# A601E.net
KiCad netlist of a schematic drawn in EAGLE
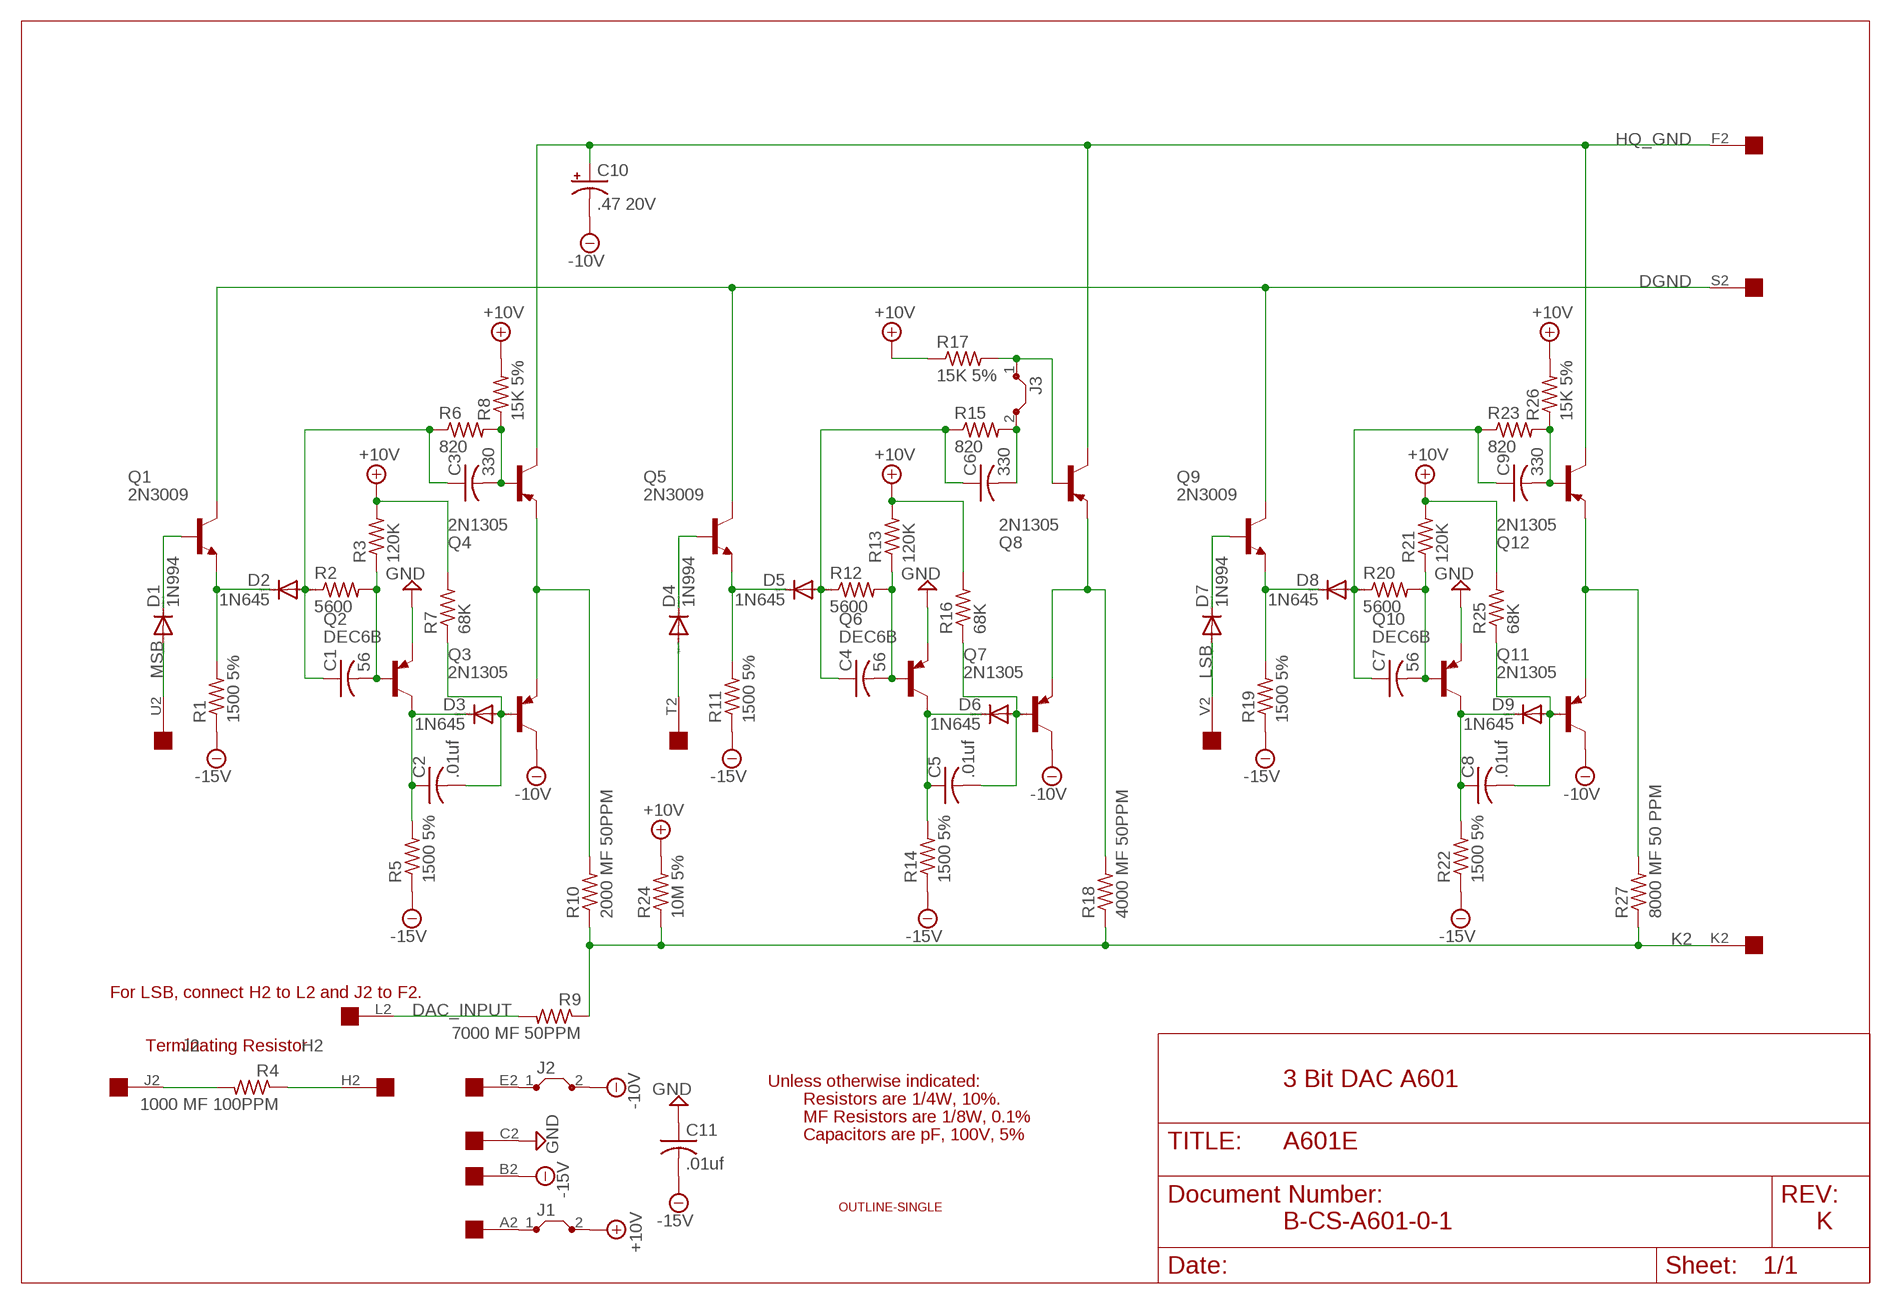
[diagram p0: schematic, sheet 1]

(export (version "E")
  (design (tool "Eeschema 10.0.6"))
  (components
    (comp (ref "C1")
      (value "56")
      (footprint "eagle-import:C075-032X103")
      (libsource (lib "eagle-import") (part "C-US075-032X103"))
    )
    (comp (ref "C2")
      (value ".01uf")
      (footprint "eagle-import:C050-025X075")
      (libsource (lib "eagle-import") (part "C-US050-025X075"))
    )
    (comp (ref "C3")
      (value "330")
      (footprint "eagle-import:C075-032X103")
      (libsource (lib "eagle-import") (part "C-US075-032X103"))
    )
    (comp (ref "C4")
      (value "56")
      (footprint "eagle-import:C075-032X103")
      (libsource (lib "eagle-import") (part "C-US075-032X103"))
    )
    (comp (ref "C5")
      (value ".01uf")
      (footprint "eagle-import:C050-025X075")
      (libsource (lib "eagle-import") (part "C-US050-025X075"))
    )
    (comp (ref "C6")
      (value "330")
      (footprint "eagle-import:C075-032X103")
      (libsource (lib "eagle-import") (part "C-US075-032X103"))
    )
    (comp (ref "C7")
      (value "56")
      (footprint "eagle-import:C075-032X103")
      (libsource (lib "eagle-import") (part "C-US075-032X103"))
    )
    (comp (ref "C8")
      (value ".01uf")
      (footprint "eagle-import:C050-025X075")
      (libsource (lib "eagle-import") (part "C-US050-025X075"))
    )
    (comp (ref "C9")
      (value "330")
      (footprint "eagle-import:C075-032X103")
      (libsource (lib "eagle-import") (part "C-US075-032X103"))
    )
    (comp (ref "C10")
      (value ".47 20V")
      (footprint "eagle-import:E22-6")
      (libsource (lib "eagle-import") (part "CPOL-USE22-6AXIAL"))
    )
    (comp (ref "C11")
      (value ".01uf")
      (footprint "eagle-import:C050-025X075")
      (libsource (lib "eagle-import") (part "C-US050-025X075"))
    )
    (comp (ref "D1")
      (value "1N994")
      (footprint "eagle-import:DO35-10")
      (libsource (lib "eagle-import") (part "1N4148DO35-10"))
    )
    (comp (ref "D2")
      (value "1N645")
      (footprint "eagle-import:DO35-10")
      (libsource (lib "eagle-import") (part "1N4148DO35-10"))
    )
    (comp (ref "D3")
      (value "1N645")
      (footprint "eagle-import:DO35-10")
      (libsource (lib "eagle-import") (part "1N4148DO35-10"))
    )
    (comp (ref "D4")
      (value "1N994")
      (footprint "eagle-import:DO35-10")
      (libsource (lib "eagle-import") (part "1N4148DO35-10"))
    )
    (comp (ref "D5")
      (value "1N645")
      (footprint "eagle-import:DO35-10")
      (libsource (lib "eagle-import") (part "1N4148DO35-10"))
    )
    (comp (ref "D6")
      (value "1N645")
      (footprint "eagle-import:DO35-10")
      (libsource (lib "eagle-import") (part "1N4148DO35-10"))
    )
    (comp (ref "D7")
      (value "1N994")
      (footprint "eagle-import:DO35-10")
      (libsource (lib "eagle-import") (part "1N4148DO35-10"))
    )
    (comp (ref "D8")
      (value "1N645")
      (footprint "eagle-import:DO35-10")
      (libsource (lib "eagle-import") (part "1N4148DO35-10"))
    )
    (comp (ref "D9")
      (value "1N645")
      (footprint "eagle-import:DO35-10")
      (libsource (lib "eagle-import") (part "1N4148DO35-10"))
    )
    (comp (ref "J1")
      (value "J10MM")
      (footprint "eagle-import:10")
      (libsource (lib "eagle-import") (part "J10MM"))
    )
    (comp (ref "J2")
      (value "J10MM")
      (footprint "eagle-import:10")
      (libsource (lib "eagle-import") (part "J10MM"))
    )
    (comp (ref "J3")
      (value "J10MM")
      (footprint "eagle-import:10")
      (libsource (lib "eagle-import") (part "J10MM"))
    )
    (comp (ref "Q1")
      (value "2N3009")
      (footprint "eagle-import:TO39")
      (libsource (lib "eagle-import") (part "-NPN-TO39-EBC2N1613"))
    )
    (comp (ref "Q2")
      (value "DEC6B")
      (footprint "eagle-import:TO39")
      (libsource (lib "eagle-import") (part "2N2904A"))
    )
    (comp (ref "Q3")
      (value "2N1305")
      (footprint "eagle-import:TO39")
      (libsource (lib "eagle-import") (part "2N2904A"))
    )
    (comp (ref "Q4")
      (value "2N1305")
      (footprint "eagle-import:TO39")
      (libsource (lib "eagle-import") (part "2N2904A"))
    )
    (comp (ref "Q5")
      (value "2N3009")
      (footprint "eagle-import:TO39")
      (libsource (lib "eagle-import") (part "-NPN-TO39-EBC2N1613"))
    )
    (comp (ref "Q6")
      (value "DEC6B")
      (footprint "eagle-import:TO39")
      (libsource (lib "eagle-import") (part "2N2904A"))
    )
    (comp (ref "Q7")
      (value "2N1305")
      (footprint "eagle-import:TO39")
      (libsource (lib "eagle-import") (part "2N2904A"))
    )
    (comp (ref "Q8")
      (value "2N1305")
      (footprint "eagle-import:TO39")
      (libsource (lib "eagle-import") (part "2N2904A"))
    )
    (comp (ref "Q9")
      (value "2N3009")
      (footprint "eagle-import:TO39")
      (libsource (lib "eagle-import") (part "-NPN-TO39-EBC2N1613"))
    )
    (comp (ref "Q10")
      (value "DEC6B")
      (footprint "eagle-import:TO39")
      (libsource (lib "eagle-import") (part "2N2904A"))
    )
    (comp (ref "Q11")
      (value "2N1305")
      (footprint "eagle-import:TO39")
      (libsource (lib "eagle-import") (part "2N2904A"))
    )
    (comp (ref "Q12")
      (value "2N1305")
      (footprint "eagle-import:TO39")
      (libsource (lib "eagle-import") (part "2N2904A"))
    )
    (comp (ref "R1")
      (value "1500 5%")
      (footprint "eagle-import:0207_10")
      (libsource (lib "eagle-import") (part "R-US_0207/10"))
    )
    (comp (ref "R2")
      (value "5600")
      (footprint "eagle-import:0207_10")
      (libsource (lib "eagle-import") (part "R-US_0207/10"))
    )
    (comp (ref "R3")
      (value "120K")
      (footprint "eagle-import:0207_10")
      (libsource (lib "eagle-import") (part "R-US_0207/10"))
    )
    (comp (ref "R4")
      (value "1000 MF 100PPM")
      (footprint "eagle-import:0309_12")
      (libsource (lib "eagle-import") (part "R-US_0309/12"))
    )
    (comp (ref "R5")
      (value "1500 5%")
      (footprint "eagle-import:0207_10")
      (libsource (lib "eagle-import") (part "R-US_0207/10"))
    )
    (comp (ref "R6")
      (value "820")
      (footprint "eagle-import:0207_10")
      (libsource (lib "eagle-import") (part "R-US_0207/10"))
    )
    (comp (ref "R7")
      (value "68K")
      (footprint "eagle-import:0207_10")
      (libsource (lib "eagle-import") (part "R-US_0207/10"))
    )
    (comp (ref "R8")
      (value "15K 5%")
      (footprint "eagle-import:0207_10")
      (libsource (lib "eagle-import") (part "R-US_0207/10"))
    )
    (comp (ref "R9")
      (value "7000 MF 50PPM")
      (footprint "eagle-import:0309_12")
      (libsource (lib "eagle-import") (part "R-US_0309/12"))
    )
    (comp (ref "R10")
      (value "2000 MF 50PPM")
      (footprint "eagle-import:0309_12")
      (libsource (lib "eagle-import") (part "R-US_0309/12"))
    )
    (comp (ref "R11")
      (value "1500 5%")
      (footprint "eagle-import:0207_10")
      (libsource (lib "eagle-import") (part "R-US_0207/10"))
    )
    (comp (ref "R12")
      (value "5600")
      (footprint "eagle-import:0207_10")
      (libsource (lib "eagle-import") (part "R-US_0207/10"))
    )
    (comp (ref "R13")
      (value "120K")
      (footprint "eagle-import:0207_10")
      (libsource (lib "eagle-import") (part "R-US_0207/10"))
    )
    (comp (ref "R14")
      (value "1500 5%")
      (footprint "eagle-import:0207_10")
      (libsource (lib "eagle-import") (part "R-US_0207/10"))
    )
    (comp (ref "R15")
      (value "820")
      (footprint "eagle-import:0207_10")
      (libsource (lib "eagle-import") (part "R-US_0207/10"))
    )
    (comp (ref "R16")
      (value "68K")
      (footprint "eagle-import:0207_10")
      (libsource (lib "eagle-import") (part "R-US_0207/10"))
    )
    (comp (ref "R17")
      (value "15K 5%")
      (footprint "eagle-import:0207_10")
      (libsource (lib "eagle-import") (part "R-US_0207/10"))
    )
    (comp (ref "R18")
      (value "4000 MF 50PPM")
      (footprint "eagle-import:0309_12")
      (libsource (lib "eagle-import") (part "R-US_0309/12"))
    )
    (comp (ref "R19")
      (value "1500 5%")
      (footprint "eagle-import:0207_10")
      (libsource (lib "eagle-import") (part "R-US_0207/10"))
    )
    (comp (ref "R20")
      (value "5600")
      (footprint "eagle-import:0207_10")
      (libsource (lib "eagle-import") (part "R-US_0207/10"))
    )
    (comp (ref "R21")
      (value "120K")
      (footprint "eagle-import:0207_10")
      (libsource (lib "eagle-import") (part "R-US_0207/10"))
    )
    (comp (ref "R22")
      (value "1500 5%")
      (footprint "eagle-import:0207_10")
      (libsource (lib "eagle-import") (part "R-US_0207/10"))
    )
    (comp (ref "R23")
      (value "820")
      (footprint "eagle-import:0207_10")
      (libsource (lib "eagle-import") (part "R-US_0207/10"))
    )
    (comp (ref "R24")
      (value "10M 5%")
      (footprint "eagle-import:0207_10")
      (libsource (lib "eagle-import") (part "R-US_0207/10"))
    )
    (comp (ref "R25")
      (value "68K")
      (footprint "eagle-import:0207_10")
      (libsource (lib "eagle-import") (part "R-US_0207/10"))
    )
    (comp (ref "R26")
      (value "15K 5%")
      (footprint "eagle-import:0207_10")
      (libsource (lib "eagle-import") (part "R-US_0207/10"))
    )
    (comp (ref "R27")
      (value "8000 MF 50 PPM")
      (footprint "eagle-import:0309_12")
      (libsource (lib "eagle-import") (part "R-US_0309/12"))
    )
    (comp (ref "U$1")
      (value "OUTLINE-SINGLE")
      (footprint "eagle-import:SINGLE")
      (libsource (lib "eagle-import") (part "OUTLINE-SINGLE"))
    )
    (comp (ref "U$3")
      (value "EDGE-1")
      (footprint "eagle-import:EDGE-CON1")
      (libsource (lib "eagle-import") (part "EDGE-1"))
    )
  )
  (nets
    (net (code "1") (name "+10V") (class "Default")
      (node (ref "J1") (pin "2") (pinfunction "2_2") (pintype "passive"))
      (node (ref "R13") (pin "2") (pinfunction "2_2") (pintype "passive"))
      (node (ref "R16") (pin "2") (pinfunction "2_2") (pintype "passive"))
      (node (ref "R17") (pin "1") (pinfunction "1_1") (pintype "passive"))
      (node (ref "R21") (pin "2") (pinfunction "2_2") (pintype "passive"))
      (node (ref "R24") (pin "2") (pinfunction "2_2") (pintype "passive"))
      (node (ref "R25") (pin "2") (pinfunction "2_2") (pintype "passive"))
      (node (ref "R26") (pin "2") (pinfunction "2_2") (pintype "passive"))
      (node (ref "R3") (pin "2") (pinfunction "2_2") (pintype "passive"))
      (node (ref "R7") (pin "2") (pinfunction "2_2") (pintype "passive"))
      (node (ref "R8") (pin "2") (pinfunction "2_2") (pintype "passive"))
    )
    (net (code "2") (name "-10V") (class "Default")
      (node (ref "C10") (pin "-") (pinfunction "-_-") (pintype "passive"))
      (node (ref "J2") (pin "2") (pinfunction "2_2") (pintype "passive"))
      (node (ref "Q11") (pin "3") (pinfunction "C_3") (pintype "passive"))
      (node (ref "Q3") (pin "3") (pinfunction "C_3") (pintype "passive"))
      (node (ref "Q7") (pin "3") (pinfunction "C_3") (pintype "passive"))
    )
    (net (code "3") (name "-15V") (class "Default")
      (node (ref "C11") (pin "2") (pinfunction "2_2") (pintype "passive"))
      (node (ref "R1") (pin "1") (pinfunction "1_1") (pintype "passive"))
      (node (ref "R11") (pin "1") (pinfunction "1_1") (pintype "passive"))
      (node (ref "R14") (pin "1") (pinfunction "1_1") (pintype "passive"))
      (node (ref "R19") (pin "1") (pinfunction "1_1") (pintype "passive"))
      (node (ref "R22") (pin "1") (pinfunction "1_1") (pintype "passive"))
      (node (ref "R5") (pin "1") (pinfunction "1_1") (pintype "passive"))
      (node (ref "U$3") (pin "B2") (pinfunction "1_B2") (pintype "bidirectional"))
    )
    (net (code "4") (name "/DAC_INPUT") (class "Default")
      (node (ref "R9") (pin "2") (pinfunction "2_2") (pintype "passive"))
      (node (ref "U$3") (pin "L2") (pinfunction "1_L2") (pintype "bidirectional"))
    )
    (net (code "5") (name "/DGND") (class "Default")
      (node (ref "Q1") (pin "3") (pinfunction "C_3") (pintype "passive"))
      (node (ref "Q5") (pin "3") (pinfunction "C_3") (pintype "passive"))
      (node (ref "Q9") (pin "3") (pinfunction "C_3") (pintype "passive"))
      (node (ref "U$3") (pin "S2") (pinfunction "1_S2") (pintype "bidirectional"))
    )
    (net (code "6") (name "/H2") (class "Default")
      (node (ref "R4") (pin "1") (pinfunction "1_1") (pintype "passive"))
      (node (ref "U$3") (pin "H2") (pinfunction "1_H2") (pintype "bidirectional"))
    )
    (net (code "7") (name "/HQ_GND") (class "Default")
      (node (ref "C10") (pin "+") (pinfunction "+_+") (pintype "passive"))
      (node (ref "Q12") (pin "3") (pinfunction "C_3") (pintype "passive"))
      (node (ref "Q4") (pin "3") (pinfunction "C_3") (pintype "passive"))
      (node (ref "Q8") (pin "3") (pinfunction "C_3") (pintype "passive"))
      (node (ref "U$3") (pin "F2") (pinfunction "1_F2") (pintype "bidirectional"))
    )
    (net (code "8") (name "/J2") (class "Default")
      (node (ref "R4") (pin "2") (pinfunction "2_2") (pintype "passive"))
      (node (ref "U$3") (pin "J2") (pinfunction "1_J2") (pintype "bidirectional"))
    )
    (net (code "9") (name "/K2") (class "Default")
      (node (ref "R10") (pin "1") (pinfunction "1_1") (pintype "passive"))
      (node (ref "R18") (pin "1") (pinfunction "1_1") (pintype "passive"))
      (node (ref "R24") (pin "1") (pinfunction "1_1") (pintype "passive"))
      (node (ref "R27") (pin "1") (pinfunction "1_1") (pintype "passive"))
      (node (ref "R9") (pin "1") (pinfunction "1_1") (pintype "passive"))
      (node (ref "U$3") (pin "K2") (pinfunction "1_K2") (pintype "bidirectional"))
    )
    (net (code "10") (name "/LSB") (class "Default")
      (node (ref "D7") (pin "A") (pinfunction "A_A") (pintype "passive"))
      (node (ref "U$3") (pin "V2") (pinfunction "1_V2") (pintype "bidirectional"))
    )
    (net (code "11") (name "/MSB") (class "Default")
      (node (ref "D1") (pin "A") (pinfunction "A_A") (pintype "passive"))
      (node (ref "U$3") (pin "U2") (pinfunction "1_U2") (pintype "bidirectional"))
    )
    (net (code "12") (name "GND") (class "Default")
      (node (ref "C11") (pin "1") (pinfunction "1_1") (pintype "passive"))
      (node (ref "Q10") (pin "1") (pinfunction "E_1") (pintype "passive"))
      (node (ref "Q2") (pin "1") (pinfunction "E_1") (pintype "passive"))
      (node (ref "Q6") (pin "1") (pinfunction "E_1") (pintype "passive"))
      (node (ref "U$3") (pin "C2") (pinfunction "1_C2") (pintype "bidirectional"))
    )
    (net (code "13") (name "Net-(C1-Pad1)") (class "Default")
      (node (ref "C1") (pin "1") (pinfunction "1_1") (pintype "passive"))
      (node (ref "C3") (pin "1") (pinfunction "1_1") (pintype "passive"))
      (node (ref "D2") (pin "A") (pinfunction "A_A") (pintype "passive"))
      (node (ref "R2") (pin "1") (pinfunction "1_1") (pintype "passive"))
      (node (ref "R6") (pin "1") (pinfunction "1_1") (pintype "passive"))
    )
    (net (code "14") (name "Net-(C4-Pad1)") (class "Default")
      (node (ref "C4") (pin "1") (pinfunction "1_1") (pintype "passive"))
      (node (ref "C6") (pin "1") (pinfunction "1_1") (pintype "passive"))
      (node (ref "D5") (pin "A") (pinfunction "A_A") (pintype "passive"))
      (node (ref "R12") (pin "1") (pinfunction "1_1") (pintype "passive"))
      (node (ref "R15") (pin "1") (pinfunction "1_1") (pintype "passive"))
    )
    (net (code "15") (name "Net-(C6-Pad2)") (class "Default")
      (node (ref "C6") (pin "2") (pinfunction "2_2") (pintype "passive"))
      (node (ref "J3") (pin "2") (pinfunction "2_2") (pintype "passive"))
      (node (ref "R15") (pin "2") (pinfunction "2_2") (pintype "passive"))
    )
    (net (code "16") (name "Net-(C7-Pad1)") (class "Default")
      (node (ref "C7") (pin "1") (pinfunction "1_1") (pintype "passive"))
      (node (ref "C9") (pin "1") (pinfunction "1_1") (pintype "passive"))
      (node (ref "D8") (pin "A") (pinfunction "A_A") (pintype "passive"))
      (node (ref "R20") (pin "1") (pinfunction "1_1") (pintype "passive"))
      (node (ref "R23") (pin "1") (pinfunction "1_1") (pintype "passive"))
    )
    (net (code "17") (name "Net-(Q1-B)") (class "Default")
      (node (ref "D1") (pin "C") (pinfunction "C_C") (pintype "passive"))
      (node (ref "Q1") (pin "2") (pinfunction "B_2") (pintype "passive"))
    )
    (net (code "18") (name "Net-(Q1-E)") (class "Default")
      (node (ref "D2") (pin "C") (pinfunction "C_C") (pintype "passive"))
      (node (ref "Q1") (pin "1") (pinfunction "E_1") (pintype "passive"))
      (node (ref "R1") (pin "2") (pinfunction "2_2") (pintype "passive"))
    )
    (net (code "19") (name "Net-(Q2-B)") (class "Default")
      (node (ref "C1") (pin "2") (pinfunction "2_2") (pintype "passive"))
      (node (ref "Q2") (pin "2") (pinfunction "B_2") (pintype "passive"))
      (node (ref "R2") (pin "2") (pinfunction "2_2") (pintype "passive"))
      (node (ref "R3") (pin "1") (pinfunction "1_1") (pintype "passive"))
    )
    (net (code "20") (name "Net-(Q2-C)") (class "Default")
      (node (ref "C2") (pin "1") (pinfunction "1_1") (pintype "passive"))
      (node (ref "D3") (pin "C") (pinfunction "C_C") (pintype "passive"))
      (node (ref "Q2") (pin "3") (pinfunction "C_3") (pintype "passive"))
      (node (ref "R5") (pin "2") (pinfunction "2_2") (pintype "passive"))
    )
    (net (code "21") (name "Net-(Q3-B)") (class "Default")
      (node (ref "C2") (pin "2") (pinfunction "2_2") (pintype "passive"))
      (node (ref "D3") (pin "A") (pinfunction "A_A") (pintype "passive"))
      (node (ref "Q3") (pin "2") (pinfunction "B_2") (pintype "passive"))
      (node (ref "R7") (pin "1") (pinfunction "1_1") (pintype "passive"))
    )
    (net (code "22") (name "Net-(Q3-E)") (class "Default")
      (node (ref "Q3") (pin "1") (pinfunction "E_1") (pintype "passive"))
      (node (ref "Q4") (pin "1") (pinfunction "E_1") (pintype "passive"))
      (node (ref "R10") (pin "2") (pinfunction "2_2") (pintype "passive"))
    )
    (net (code "23") (name "Net-(Q4-B)") (class "Default")
      (node (ref "C3") (pin "2") (pinfunction "2_2") (pintype "passive"))
      (node (ref "Q4") (pin "2") (pinfunction "B_2") (pintype "passive"))
      (node (ref "R6") (pin "2") (pinfunction "2_2") (pintype "passive"))
      (node (ref "R8") (pin "1") (pinfunction "1_1") (pintype "passive"))
    )
    (net (code "24") (name "Net-(Q5-B)") (class "Default")
      (node (ref "D4") (pin "C") (pinfunction "C_C") (pintype "passive"))
      (node (ref "Q5") (pin "2") (pinfunction "B_2") (pintype "passive"))
    )
    (net (code "25") (name "Net-(Q5-E)") (class "Default")
      (node (ref "D5") (pin "C") (pinfunction "C_C") (pintype "passive"))
      (node (ref "Q5") (pin "1") (pinfunction "E_1") (pintype "passive"))
      (node (ref "R11") (pin "2") (pinfunction "2_2") (pintype "passive"))
    )
    (net (code "26") (name "Net-(Q6-B)") (class "Default")
      (node (ref "C4") (pin "2") (pinfunction "2_2") (pintype "passive"))
      (node (ref "Q6") (pin "2") (pinfunction "B_2") (pintype "passive"))
      (node (ref "R12") (pin "2") (pinfunction "2_2") (pintype "passive"))
      (node (ref "R13") (pin "1") (pinfunction "1_1") (pintype "passive"))
    )
    (net (code "27") (name "Net-(Q6-C)") (class "Default")
      (node (ref "C5") (pin "1") (pinfunction "1_1") (pintype "passive"))
      (node (ref "D6") (pin "C") (pinfunction "C_C") (pintype "passive"))
      (node (ref "Q6") (pin "3") (pinfunction "C_3") (pintype "passive"))
      (node (ref "R14") (pin "2") (pinfunction "2_2") (pintype "passive"))
    )
    (net (code "28") (name "Net-(Q7-B)") (class "Default")
      (node (ref "C5") (pin "2") (pinfunction "2_2") (pintype "passive"))
      (node (ref "D6") (pin "A") (pinfunction "A_A") (pintype "passive"))
      (node (ref "Q7") (pin "2") (pinfunction "B_2") (pintype "passive"))
      (node (ref "R16") (pin "1") (pinfunction "1_1") (pintype "passive"))
    )
    (net (code "29") (name "Net-(Q7-E)") (class "Default")
      (node (ref "Q7") (pin "1") (pinfunction "E_1") (pintype "passive"))
      (node (ref "Q8") (pin "1") (pinfunction "E_1") (pintype "passive"))
      (node (ref "R18") (pin "2") (pinfunction "2_2") (pintype "passive"))
    )
    (net (code "30") (name "Net-(Q8-B)") (class "Default")
      (node (ref "J3") (pin "1") (pinfunction "1_1") (pintype "passive"))
      (node (ref "Q8") (pin "2") (pinfunction "B_2") (pintype "passive"))
      (node (ref "R17") (pin "2") (pinfunction "2_2") (pintype "passive"))
    )
    (net (code "31") (name "Net-(Q9-B)") (class "Default")
      (node (ref "D7") (pin "C") (pinfunction "C_C") (pintype "passive"))
      (node (ref "Q9") (pin "2") (pinfunction "B_2") (pintype "passive"))
    )
    (net (code "32") (name "Net-(Q9-E)") (class "Default")
      (node (ref "D8") (pin "C") (pinfunction "C_C") (pintype "passive"))
      (node (ref "Q9") (pin "1") (pinfunction "E_1") (pintype "passive"))
      (node (ref "R19") (pin "2") (pinfunction "2_2") (pintype "passive"))
    )
    (net (code "33") (name "Net-(Q10-B)") (class "Default")
      (node (ref "C7") (pin "2") (pinfunction "2_2") (pintype "passive"))
      (node (ref "Q10") (pin "2") (pinfunction "B_2") (pintype "passive"))
      (node (ref "R20") (pin "2") (pinfunction "2_2") (pintype "passive"))
      (node (ref "R21") (pin "1") (pinfunction "1_1") (pintype "passive"))
    )
    (net (code "34") (name "Net-(Q10-C)") (class "Default")
      (node (ref "C8") (pin "1") (pinfunction "1_1") (pintype "passive"))
      (node (ref "D9") (pin "C") (pinfunction "C_C") (pintype "passive"))
      (node (ref "Q10") (pin "3") (pinfunction "C_3") (pintype "passive"))
      (node (ref "R22") (pin "2") (pinfunction "2_2") (pintype "passive"))
    )
    (net (code "35") (name "Net-(Q11-B)") (class "Default")
      (node (ref "C8") (pin "2") (pinfunction "2_2") (pintype "passive"))
      (node (ref "D9") (pin "A") (pinfunction "A_A") (pintype "passive"))
      (node (ref "Q11") (pin "2") (pinfunction "B_2") (pintype "passive"))
      (node (ref "R25") (pin "1") (pinfunction "1_1") (pintype "passive"))
    )
    (net (code "36") (name "Net-(Q11-E)") (class "Default")
      (node (ref "Q11") (pin "1") (pinfunction "E_1") (pintype "passive"))
      (node (ref "Q12") (pin "1") (pinfunction "E_1") (pintype "passive"))
      (node (ref "R27") (pin "2") (pinfunction "2_2") (pintype "passive"))
    )
    (net (code "37") (name "Net-(Q12-B)") (class "Default")
      (node (ref "C9") (pin "2") (pinfunction "2_2") (pintype "passive"))
      (node (ref "Q12") (pin "2") (pinfunction "B_2") (pintype "passive"))
      (node (ref "R23") (pin "2") (pinfunction "2_2") (pintype "passive"))
      (node (ref "R26") (pin "1") (pinfunction "1_1") (pintype "passive"))
    )
    (net (code "38") (name "Net-(U$3A-1)") (class "Default")
      (node (ref "J1") (pin "1") (pinfunction "1_1") (pintype "passive"))
      (node (ref "U$3") (pin "A2") (pinfunction "1_A2") (pintype "bidirectional"))
    )
    (net (code "39") (name "Net-(U$3E-1)") (class "Default")
      (node (ref "J2") (pin "1") (pinfunction "1_1") (pintype "passive"))
      (node (ref "U$3") (pin "E2") (pinfunction "1_E2") (pintype "bidirectional"))
    )
    (net (code "40") (name "Net-(U$3P-1)") (class "Default")
      (node (ref "D4") (pin "A") (pinfunction "A_A") (pintype "passive"))
      (node (ref "U$3") (pin "T2") (pinfunction "1_T2") (pintype "bidirectional"))
    )
  )
)
